# MCU.net
KiCad netlist of a schematic drawn in Altium Designer
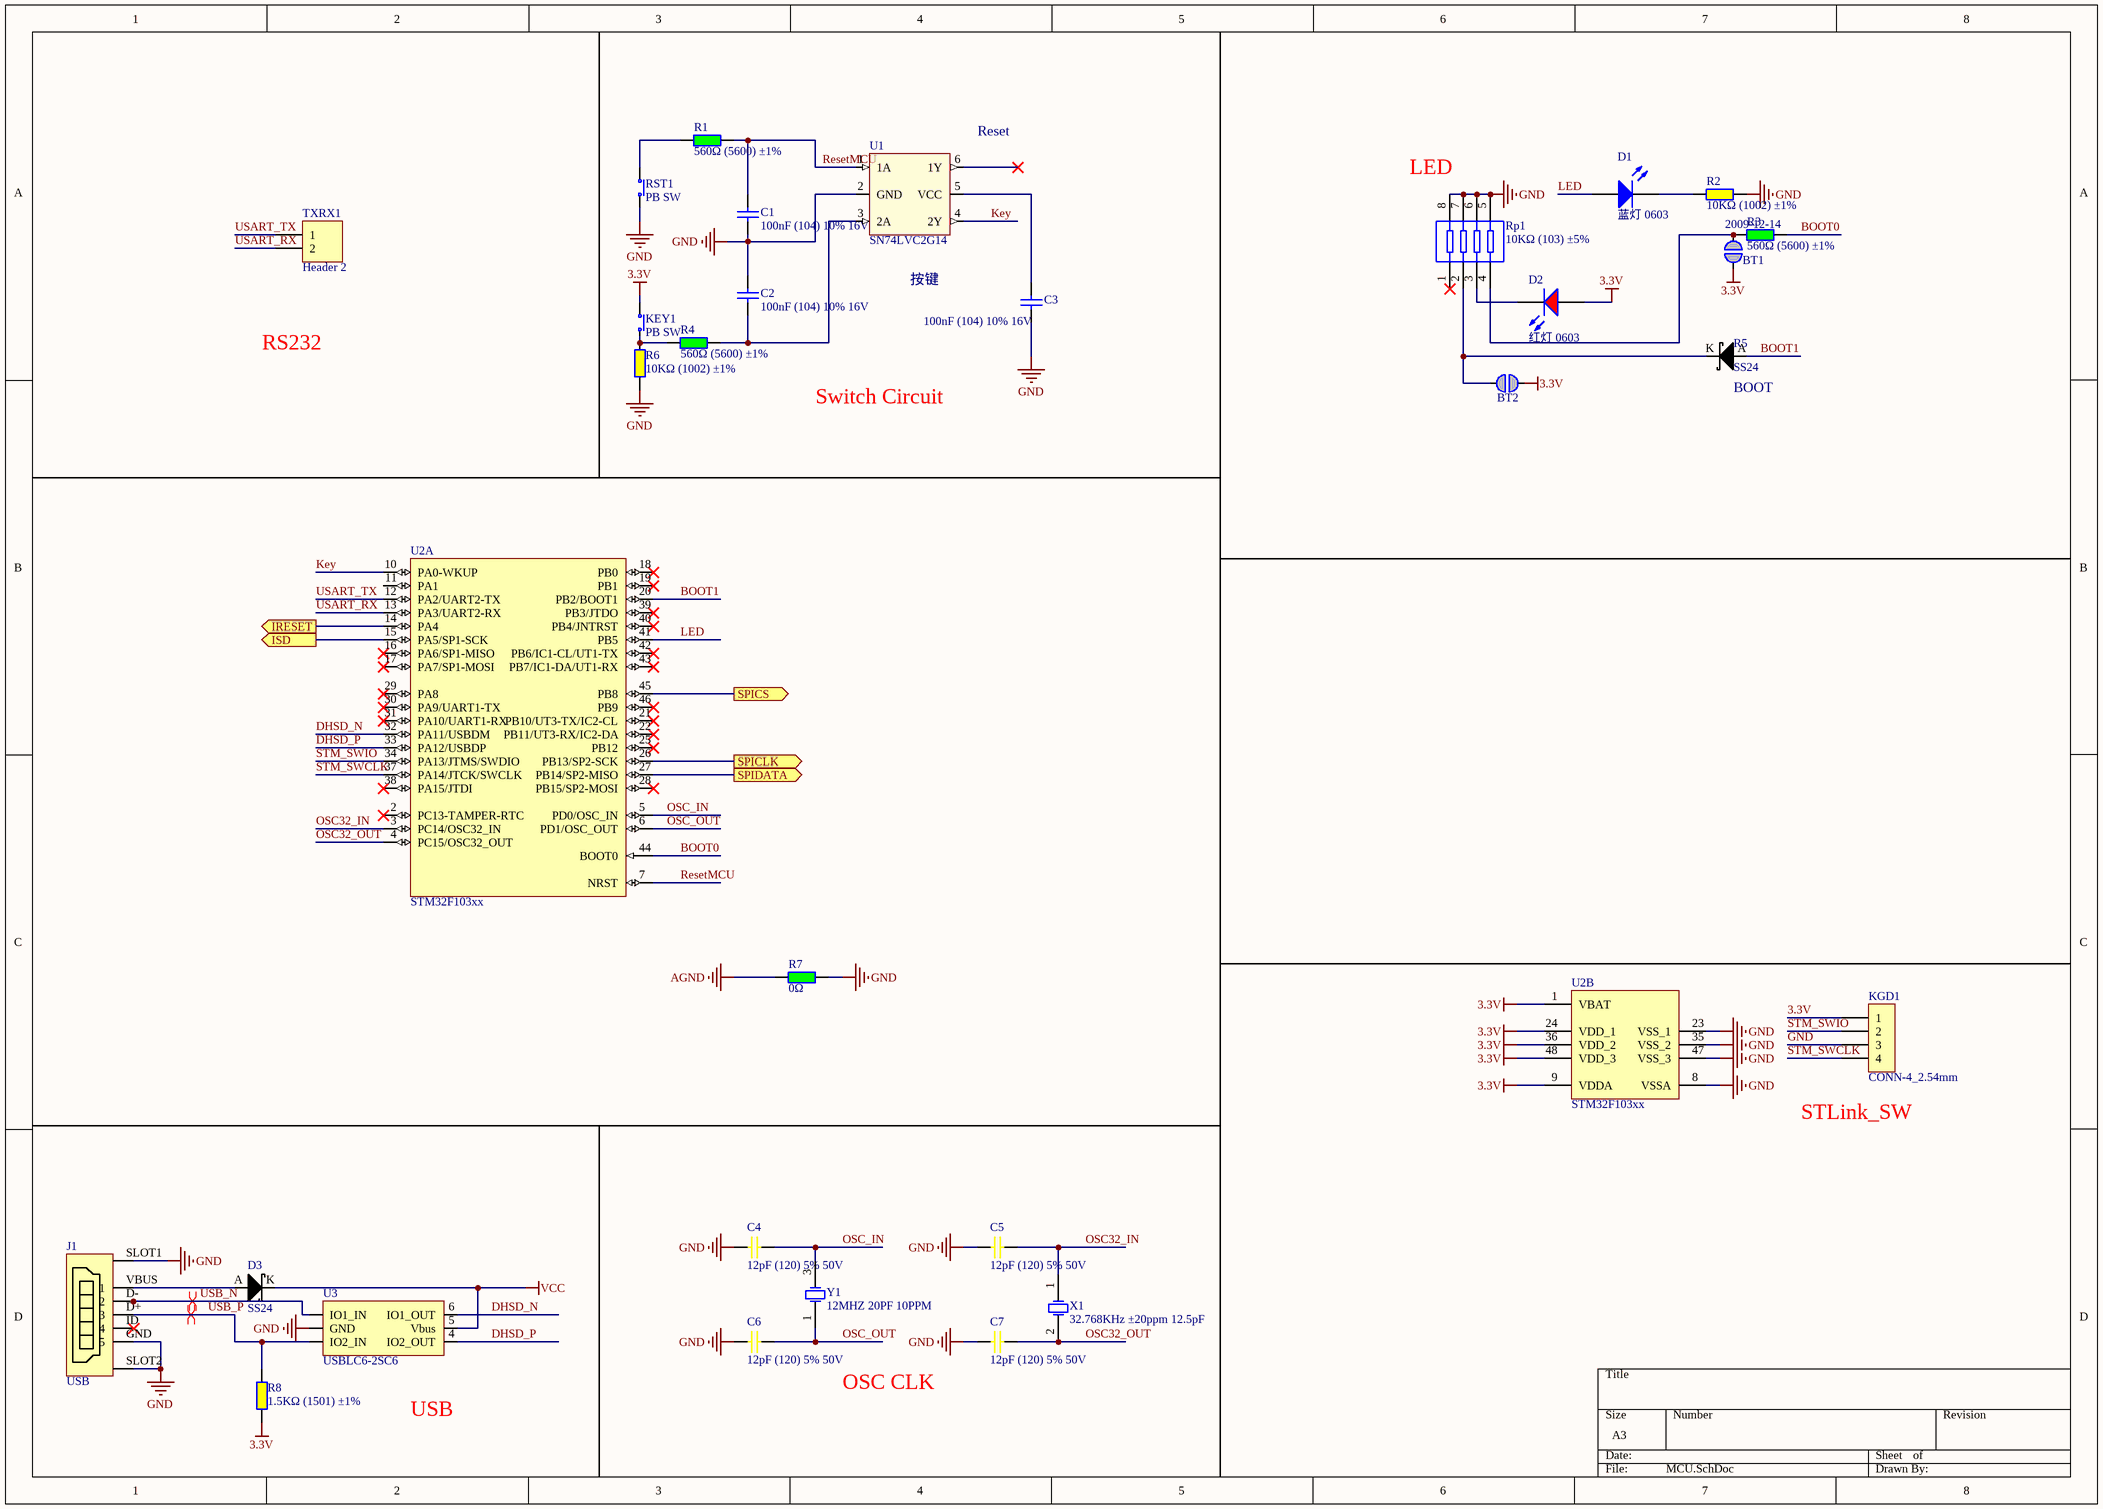
[diagram p0: MCU.SchDoc]

(export (version "E")
  (design (tool "Eeschema 10.0.6"))
  (components
    (comp (ref "BT1")
      (value "Solderbridge")
      (footprint "Solderbridge")
      (fields
        (field (name "LATESTREVISIONDATE") "2009-12-14")
        (field (name "PUBLISHER") "Nordic Semiconductor")
      )
      (libsource (lib "Schlib1") (part "SOLDERBRIDGE"))
    )
    (comp (ref "BT2")
      (value "Solderbridge")
      (footprint "Solderbridge")
      (fields (field (name "PUBLISHER") "Nordic Semiconductor"))
      (libsource (lib "Schlib1") (part "SOLDERBRIDGE"))
    )
    (comp (ref "C1")
      (value "100nF (104) 10% 16V")
      (footprint "0402_C")
      (description "贴片电容")
      (libsource (lib "Schlib1") (part "0402 100nF (104) 10% 16V"))
    )
    (comp (ref "C2")
      (value "100nF (104) 10% 16V")
      (footprint "0402_C")
      (description "贴片电容")
      (libsource (lib "Schlib1") (part "0402 100nF (104) 10% 16V"))
    )
    (comp (ref "C3")
      (value "100nF (104) 10% 16V")
      (footprint "0402_C")
      (description "贴片电容")
      (libsource (lib "Schlib1") (part "0402 100nF (104) 10% 16V"))
    )
    (comp (ref "C4")
      (value "12pF (120) 5% 50V")
      (footprint "0402_C")
      (description "贴片电容")
      (libsource (lib "Schlib1") (part "0402 12pF (120) 5% 50V"))
    )
    (comp (ref "C5")
      (value "12pF (120) 5% 50V")
      (footprint "0402_C")
      (description "贴片电容")
      (libsource (lib "Schlib1") (part "0402 12pF (120) 5% 50V"))
    )
    (comp (ref "C6")
      (value "12pF (120) 5% 50V")
      (footprint "0402_C")
      (description "贴片电容")
      (libsource (lib "Schlib1") (part "0402 12pF (120) 5% 50V"))
    )
    (comp (ref "C7")
      (value "12pF (120) 5% 50V")
      (footprint "0402_C")
      (description "贴片电容")
      (libsource (lib "Schlib1") (part "0402 12pF (120) 5% 50V"))
    )
    (comp (ref "D1")
      (value "蓝灯 0603")
      (footprint "0603_LED_S1")
      (description "发光二极管")
      (libsource (lib "LED") (part "0603 蓝灯"))
    )
    (comp (ref "D2")
      (value "红灯 0603")
      (footprint "0603_LED_S1")
      (description "发光二极管")
      (libsource (lib "LED") (part "0603 红灯"))
    )
    (comp (ref "D3")
      (value "SS24")
      (footprint "SMB-DIODE-DO214AA")
      (description "SCHOTTKY DIODE")
      (fields (field (name "MANUFACTURER") "Fairchild Semiconductor"))
      (libsource (lib "Schlib1") (part "SS24"))
    )
    (comp (ref "J1")
      (value "USB")
      (footprint "MicroUSB_SMT")
      (description "Micro-USB Type:B")
      (fields (field (name "MANUFACTURER") "精拓金"))
      (libsource (lib "Schlib1") (part "USB"))
    )
    (comp (ref "KEY1")
      (value "PB SW")
      (footprint "ALPS_SKHUxxx010_WO_GND")
      (description "Switch")
      (fields
        (field (name "MANUFACTURER") "韩国韩荣")
        (field (name "MANUFACTURER PART NUMBER") "K2-6639SP-C4SC-04")
      )
      (libsource (lib "Schlib1") (part "SW-PB_mouser"))
    )
    (comp (ref "KGD1")
      (value "CONN-4_2.54mm")
      (footprint "CON4-2.54mm")
      (description "2.54mm 4pin through hole")
      (libsource (lib "Schlib1") (part "CONN-4_2.54mm"))
    )
    (comp (ref "R1")
      (value "560Ω (5600) ±1%")
      (footprint "0603_R")
      (description "贴片电阻")
      (libsource (lib "Schlib1") (part "0603 560Ω (5600) 1%"))
    )
    (comp (ref "R2")
      (value "10KΩ (1002) ±1%")
      (footprint "0402_R")
      (description "贴片电阻")
      (libsource (lib "Schlib1") (part "0402 10KΩ (1002) 1%"))
    )
    (comp (ref "R3")
      (value "560Ω (5600) ±1%")
      (footprint "0603_R")
      (description "贴片电阻")
      (libsource (lib "Schlib1") (part "0603 560Ω (5600) 1%"))
    )
    (comp (ref "R4")
      (value "560Ω (5600) ±1%")
      (footprint "0603_R")
      (description "贴片电阻")
      (libsource (lib "Schlib1") (part "0603 560Ω (5600) 1%"))
    )
    (comp (ref "R5")
      (value "SS24")
      (footprint "SMB-DIODE-DO214AA")
      (description "SCHOTTKY DIODE")
      (fields (field (name "MANUFACTURER") "Fairchild Semiconductor"))
      (libsource (lib "Schlib1") (part "SS24"))
    )
    (comp (ref "R6")
      (value "10KΩ (1002) ±1%")
      (footprint "0402_R")
      (description "贴片电阻")
      (libsource (lib "") (part "0402 10KΩ (1002) 1%_1"))
    )
    (comp (ref "R7")
      (value "0Ω")
      (footprint "0603_R")
      (description "贴片电阻")
      (libsource (lib "Schlib1") (part "0603 0Ω"))
    )
    (comp (ref "R8")
      (value "1.5KΩ (1501) ±1%")
      (footprint "0402_R")
      (description "贴片电阻")
      (libsource (lib "Schlib1") (part "0402 1.5KΩ (1501) 1%"))
    )
    (comp (ref "Rp1")
      (value "10KΩ (103) ±5%")
      (footprint "0603_Rx4")
      (description "贴片排阻")
      (libsource (lib "Schlib1") (part "0603*4  10KΩ (103) 5%"))
    )
    (comp (ref "RST1")
      (value "PB SW")
      (footprint "ALPS_SKHUxxx010_WO_GND")
      (description "Switch")
      (fields
        (field (name "MANUFACTURER") "韩国韩荣")
        (field (name "MANUFACTURER PART NUMBER") "K2-6639SP-C4SC-04")
      )
      (libsource (lib "Schlib1") (part "SW-PB_mouser"))
    )
    (comp (ref "TXRX1")
      (value "Header 2")
      (footprint "HDR1X2")
      (description "Header, 2-Pin")
      (fields (field (name "PUBLISHER") "Altium Limited"))
      (libsource (lib "Schlib1") (part "Header 2"))
    )
    (comp (ref "U1")
      (value "SN74LVC2G14")
      (footprint "SN74LVC2G14DBVR")
      (description "74系列逻辑芯片")
      (fields (field (name "MANUFACTURER") "TI"))
      (libsource (lib "Schlib1") (part "SN74LVC2G14"))
    )
    (comp (ref "U2")
      (value "STM32F103xx")
      (footprint "PcbLib1:LQFP-48_7x7x05P")
      (description "ARM")
      (libsource (lib "Schlib1") (part "STM32F103xx"))
    )
    (comp (ref "U3")
      (value "USBLC6-2SC6")
      (footprint "SOT-23-6")
      (description "ESD二极管（静电保护）")
      (fields (field (name "MANUFACTURER") "ST"))
      (libsource (lib "Schlib1") (part "USBLC6-2SC6"))
    )
    (comp (ref "X1")
      (value "32.768KHz ±20ppm 12.5pF")
      (footprint "SMD-3215_2P FC - 135")
      (description "贴片晶振")
      (libsource (lib "CrystalOscillator") (part "SMD-3215_2P 32.768KHz 20ppm 12.5pF"))
    )
    (comp (ref "Y1")
      (value "12MHZ 20PF 10PPM")
      (footprint "SMD-3225_4P")
      (description "贴片晶振")
      (libsource (lib "CrystalOscillator") (part "SMD-3225_4P  12MHZ 20PF 10PPM"))
    )
  )
  (nets
    (net (code "1") (name "/BOOT0") (class "Default")
      (node (ref "R3") (pin "2") (pinfunction "2_2") (pintype "passive"))
      (node (ref "U2") (pin "44") (pinfunction "BOOT0_44") (pintype "input"))
    )
    (net (code "2") (name "/BOOT1") (class "Default")
      (node (ref "R5") (pin "A") (pinfunction "A_A") (pintype "passive"))
      (node (ref "U2") (pin "20") (pinfunction "PB2/BOOT1_20") (pintype "bidirectional"))
    )
    (net (code "3") (name "/DHSD_N") (class "Default")
      (node (ref "U2") (pin "32") (pinfunction "PA11/USBDM_32") (pintype "bidirectional"))
      (node (ref "U3") (pin "6") (pinfunction "IO1_OUT_6") (pintype "passive"))
    )
    (net (code "4") (name "/DHSD_P") (class "Default")
      (node (ref "U2") (pin "33") (pinfunction "PA12/USBDP_33") (pintype "bidirectional"))
      (node (ref "U3") (pin "4") (pinfunction "IO2_OUT_4") (pintype "passive"))
    )
    (net (code "5") (name "/IRESET") (class "Default")
      (node (ref "U2") (pin "14") (pinfunction "PA4_14") (pintype "bidirectional"))
    )
    (net (code "6") (name "/ISD") (class "Default")
      (node (ref "U2") (pin "15") (pinfunction "PA5/SP1-SCK_15") (pintype "bidirectional"))
    )
    (net (code "7") (name "/Key") (class "Default")
      (node (ref "U1") (pin "4") (pinfunction "2Y_4") (pintype "output"))
      (node (ref "U2") (pin "10") (pinfunction "PA0-WKUP_10") (pintype "bidirectional"))
    )
    (net (code "8") (name "/LED") (class "Default")
      (node (ref "D1") (pin "A") (pinfunction "A_A") (pintype "passive"))
      (node (ref "U2") (pin "41") (pinfunction "PB5_41") (pintype "bidirectional"))
    )
    (net (code "9") (name "/OSC32_IN") (class "Default")
      (node (ref "C5") (pin "2") (pinfunction "2_2") (pintype "passive"))
      (node (ref "U2") (pin "3") (pinfunction "PC14/OSC32_IN_3") (pintype "bidirectional"))
      (node (ref "X1") (pin "1") (pinfunction "OSC1_1") (pintype "passive"))
    )
    (net (code "10") (name "/OSC32_OUT") (class "Default")
      (node (ref "C7") (pin "2") (pinfunction "2_2") (pintype "passive"))
      (node (ref "U2") (pin "4") (pinfunction "PC15/OSC32_OUT_4") (pintype "bidirectional"))
      (node (ref "X1") (pin "2") (pinfunction "OSC2_2") (pintype "passive"))
    )
    (net (code "11") (name "/OSC_IN") (class "Default")
      (node (ref "C4") (pin "2") (pinfunction "2_2") (pintype "passive"))
      (node (ref "U2") (pin "5") (pinfunction "PD0/OSC_IN_5") (pintype "bidirectional"))
      (node (ref "Y1") (pin "3") (pinfunction "OSC2_3") (pintype "passive"))
    )
    (net (code "12") (name "/OSC_OUT") (class "Default")
      (node (ref "C6") (pin "2") (pinfunction "2_2") (pintype "passive"))
      (node (ref "U2") (pin "6") (pinfunction "PD1/OSC_OUT_6") (pintype "bidirectional"))
      (node (ref "Y1") (pin "1") (pinfunction "OSC1_1") (pintype "passive"))
    )
    (net (code "13") (name "/ResetMCU") (class "Default")
      (node (ref "C1") (pin "2") (pinfunction "2_2") (pintype "passive"))
      (node (ref "R1") (pin "2") (pinfunction "2_2") (pintype "passive"))
      (node (ref "U1") (pin "1") (pinfunction "1A_1") (pintype "input"))
      (node (ref "U2") (pin "7") (pinfunction "NRST_7") (pintype "bidirectional"))
    )
    (net (code "14") (name "/SPICLK") (class "Default")
      (node (ref "U2") (pin "26") (pinfunction "PB13/SP2-SCK_26") (pintype "bidirectional"))
    )
    (net (code "15") (name "/SPICS") (class "Default")
      (node (ref "U2") (pin "45") (pinfunction "PB8_45") (pintype "bidirectional"))
    )
    (net (code "16") (name "/SPIDATA") (class "Default")
      (node (ref "U2") (pin "27") (pinfunction "PB14/SP2-MISO_27") (pintype "bidirectional"))
    )
    (net (code "17") (name "/STM_SWCLK") (class "Default")
      (node (ref "KGD1") (pin "4") (pinfunction "4_4") (pintype "passive"))
      (node (ref "U2") (pin "37") (pinfunction "PA14/JTCK/SWCLK_37") (pintype "bidirectional"))
    )
    (net (code "18") (name "/STM_SWIO") (class "Default")
      (node (ref "KGD1") (pin "2") (pinfunction "2_2") (pintype "passive"))
      (node (ref "U2") (pin "34") (pinfunction "PA13/JTMS/SWDIO_34") (pintype "bidirectional"))
    )
    (net (code "19") (name "/USART_RX") (class "Default")
      (node (ref "TXRX1") (pin "2") (pinfunction "2_2") (pintype "passive"))
      (node (ref "U2") (pin "13") (pinfunction "PA3/UART2-RX_13") (pintype "bidirectional"))
    )
    (net (code "20") (name "/USART_TX") (class "Default")
      (node (ref "TXRX1") (pin "1") (pinfunction "1_1") (pintype "passive"))
      (node (ref "U2") (pin "12") (pinfunction "PA2/UART2-TX_12") (pintype "bidirectional"))
    )
    (net (code "21") (name "/USB_N") (class "Default")
      (node (ref "J1") (pin "D-") (pinfunction "2_D-") (pintype "passive"))
      (node (ref "U3") (pin "1") (pinfunction "IO1_IN_1") (pintype "passive"))
    )
    (net (code "22") (name "/USB_P") (class "Default")
      (node (ref "J1") (pin "D+") (pinfunction "3_D+") (pintype "passive"))
      (node (ref "R8") (pin "2") (pinfunction "2_2") (pintype "passive"))
      (node (ref "U3") (pin "3") (pinfunction "IO2_IN_3") (pintype "passive"))
    )
    (net (code "23") (name "3.3V") (class "Default")
      (node (ref "BT1") (pin "2") (pinfunction "1_2") (pintype "passive"))
      (node (ref "BT2") (pin "1") (pinfunction "0_1") (pintype "passive"))
      (node (ref "D2") (pin "A") (pinfunction "A_A") (pintype "passive"))
      (node (ref "KEY1") (pin "2") (pinfunction "COM_2") (pintype "passive"))
      (node (ref "KGD1") (pin "1") (pinfunction "1_1") (pintype "passive"))
      (node (ref "R8") (pin "1") (pinfunction "1_1") (pintype "passive"))
      (node (ref "U2") (pin "1") (pinfunction "VBAT_1") (pintype "power_in"))
      (node (ref "U2") (pin "24") (pinfunction "VDD_1_24") (pintype "power_in"))
      (node (ref "U2") (pin "36") (pinfunction "VDD_2_36") (pintype "power_in"))
      (node (ref "U2") (pin "48") (pinfunction "VDD_3_48") (pintype "power_in"))
      (node (ref "U2") (pin "9") (pinfunction "VDDA_9") (pintype "power_in"))
    )
    (net (code "24") (name "AGND") (class "Default")
      (node (ref "R7") (pin "1") (pinfunction "1_1") (pintype "passive"))
    )
    (net (code "25") (name "GND") (class "Default")
      (node (ref "C1") (pin "1") (pinfunction "1_1") (pintype "passive"))
      (node (ref "C2") (pin "2") (pinfunction "2_2") (pintype "passive"))
      (node (ref "C3") (pin "1") (pinfunction "1_1") (pintype "passive"))
      (node (ref "C4") (pin "1") (pinfunction "1_1") (pintype "passive"))
      (node (ref "C5") (pin "1") (pinfunction "1_1") (pintype "passive"))
      (node (ref "C6") (pin "1") (pinfunction "1_1") (pintype "passive"))
      (node (ref "C7") (pin "1") (pinfunction "1_1") (pintype "passive"))
      (node (ref "J1") (pin "GND") (pinfunction "5_GND") (pintype "passive"))
      (node (ref "J1") (pin "SLOT1") (pinfunction "SLOT1_SLOT1") (pintype "passive"))
      (node (ref "J1") (pin "SLOT2") (pinfunction "SLOT2_SLOT2") (pintype "passive"))
      (node (ref "KGD1") (pin "3") (pinfunction "3_3") (pintype "passive"))
      (node (ref "R2") (pin "2") (pinfunction "2_2") (pintype "passive"))
      (node (ref "R6") (pin "1") (pinfunction "1_1") (pintype "passive"))
      (node (ref "R7") (pin "2") (pinfunction "2_2") (pintype "passive"))
      (node (ref "RST1") (pin "1") (pinfunction "N.O_1") (pintype "passive"))
      (node (ref "Rp1") (pin "5") (pinfunction "5_5") (pintype "passive"))
      (node (ref "Rp1") (pin "6") (pinfunction "6_6") (pintype "passive"))
      (node (ref "Rp1") (pin "7") (pinfunction "7_7") (pintype "passive"))
      (node (ref "Rp1") (pin "8") (pinfunction "8_8") (pintype "passive"))
      (node (ref "U1") (pin "2") (pinfunction "GND_2") (pintype "passive"))
      (node (ref "U2") (pin "23") (pinfunction "VSS_1_23") (pintype "power_in"))
      (node (ref "U2") (pin "35") (pinfunction "VSS_2_35") (pintype "power_in"))
      (node (ref "U2") (pin "47") (pinfunction "VSS_3_47") (pintype "power_in"))
      (node (ref "U2") (pin "8") (pinfunction "VSSA_8") (pintype "power_in"))
      (node (ref "U3") (pin "2") (pinfunction "GND_2") (pintype "passive"))
    )
    (net (code "26") (name "Net-(BT1-0)") (class "Default")
      (node (ref "BT1") (pin "1") (pinfunction "0_1") (pintype "passive"))
      (node (ref "R3") (pin "1") (pinfunction "1_1") (pintype "passive"))
      (node (ref "Rp1") (pin "4") (pinfunction "4_4") (pintype "passive"))
    )
    (net (code "27") (name "Net-(BT2-1)") (class "Default")
      (node (ref "BT2") (pin "2") (pinfunction "1_2") (pintype "passive"))
      (node (ref "R5") (pin "K") (pinfunction "K_K") (pintype "passive"))
      (node (ref "Rp1") (pin "2") (pinfunction "2_2") (pintype "passive"))
    )
    (net (code "28") (name "Net-(D1-PadK)") (class "Default")
      (node (ref "D1") (pin "K") (pinfunction "K_K") (pintype "passive"))
      (node (ref "R2") (pin "1") (pinfunction "1_1") (pintype "passive"))
    )
    (net (code "29") (name "Net-(D2-PadK)") (class "Default")
      (node (ref "D2") (pin "K") (pinfunction "K_K") (pintype "passive"))
      (node (ref "Rp1") (pin "3") (pinfunction "3_3") (pintype "passive"))
    )
    (net (code "30") (name "Net-(J1-1)") (class "Default")
      (node (ref "D3") (pin "A") (pinfunction "A_A") (pintype "passive"))
      (node (ref "J1") (pin "VBUS") (pinfunction "1_VBUS") (pintype "passive"))
    )
    (net (code "31") (name "Net-(KEY1-N.O)") (class "Default")
      (node (ref "KEY1") (pin "1") (pinfunction "N.O_1") (pintype "passive"))
      (node (ref "R4") (pin "1") (pinfunction "1_1") (pintype "passive"))
      (node (ref "R6") (pin "2") (pinfunction "2_2") (pintype "passive"))
    )
    (net (code "32") (name "Net-(RST1-COM)") (class "Default")
      (node (ref "R1") (pin "1") (pinfunction "1_1") (pintype "passive"))
      (node (ref "RST1") (pin "2") (pinfunction "COM_2") (pintype "passive"))
    )
    (net (code "33") (name "Net-(U1-2A)") (class "Default")
      (node (ref "C2") (pin "1") (pinfunction "1_1") (pintype "passive"))
      (node (ref "R4") (pin "2") (pinfunction "2_2") (pintype "passive"))
      (node (ref "U1") (pin "3") (pinfunction "2A_3") (pintype "input"))
    )
    (net (code "34") (name "Net-(U1-VCC)") (class "Default")
      (node (ref "C3") (pin "2") (pinfunction "2_2") (pintype "passive"))
      (node (ref "U1") (pin "5") (pinfunction "VCC_5") (pintype "power_in"))
    )
    (net (code "35") (name "VCC") (class "Default")
      (node (ref "D3") (pin "K") (pinfunction "K_K") (pintype "passive"))
      (node (ref "U3") (pin "5") (pinfunction "Vbus_5") (pintype "passive"))
    )
    (net (code "36") (name "unconnected-(J1-4-PadID)") (class "Default")
      (node (ref "J1") (pin "ID") (pinfunction "4_ID") (pintype "passive+no_connect"))
    )
    (net (code "37") (name "unconnected-(Rp1-Pad1)") (class "Default")
      (node (ref "Rp1") (pin "1") (pinfunction "1_1") (pintype "passive+no_connect"))
    )
    (net (code "38") (name "unconnected-(U1-1Y-Pad6)") (class "Default")
      (node (ref "U1") (pin "6") (pinfunction "1Y_6") (pintype "output+no_connect"))
    )
    (net (code "39") (name "unconnected-(U2A-PA1-Pad11)") (class "Default")
      (node (ref "U2") (pin "11") (pinfunction "PA1_11") (pintype "bidirectional"))
    )
    (net (code "40") (name "unconnected-(U2A-PA6{slash}SP1-MISO-Pad16)") (class "Default")
      (node (ref "U2") (pin "16") (pinfunction "PA6/SP1-MISO_16") (pintype "bidirectional+no_connect"))
    )
    (net (code "41") (name "unconnected-(U2A-PA7{slash}SP1-MOSI-Pad17)") (class "Default")
      (node (ref "U2") (pin "17") (pinfunction "PA7/SP1-MOSI_17") (pintype "bidirectional+no_connect"))
    )
    (net (code "42") (name "unconnected-(U2A-PA8-Pad29)") (class "Default")
      (node (ref "U2") (pin "29") (pinfunction "PA8_29") (pintype "bidirectional+no_connect"))
    )
    (net (code "43") (name "unconnected-(U2A-PA9{slash}UART1-TX-Pad30)") (class "Default")
      (node (ref "U2") (pin "30") (pinfunction "PA9/UART1-TX_30") (pintype "bidirectional+no_connect"))
    )
    (net (code "44") (name "unconnected-(U2A-PA10{slash}UART1-RX-Pad31)") (class "Default")
      (node (ref "U2") (pin "31") (pinfunction "PA10/UART1-RX_31") (pintype "bidirectional+no_connect"))
    )
    (net (code "45") (name "unconnected-(U2A-PA15{slash}JTDI-Pad38)") (class "Default")
      (node (ref "U2") (pin "38") (pinfunction "PA15/JTDI_38") (pintype "bidirectional+no_connect"))
    )
    (net (code "46") (name "unconnected-(U2A-PB0-Pad18)") (class "Default")
      (node (ref "U2") (pin "18") (pinfunction "PB0_18") (pintype "bidirectional+no_connect"))
    )
    (net (code "47") (name "unconnected-(U2A-PB1-Pad19)") (class "Default")
      (node (ref "U2") (pin "19") (pinfunction "PB1_19") (pintype "bidirectional+no_connect"))
    )
    (net (code "48") (name "unconnected-(U2A-PB3{slash}JTDO-Pad39)") (class "Default")
      (node (ref "U2") (pin "39") (pinfunction "PB3/JTDO_39") (pintype "bidirectional+no_connect"))
    )
    (net (code "49") (name "unconnected-(U2A-PB4{slash}JNTRST-Pad40)") (class "Default")
      (node (ref "U2") (pin "40") (pinfunction "PB4/JNTRST_40") (pintype "bidirectional+no_connect"))
    )
    (net (code "50") (name "unconnected-(U2A-PB6{slash}IC1-CL{slash}UT1-TX-Pad42)") (class "Default")
      (node (ref "U2") (pin "42") (pinfunction "PB6/IC1-CL/UT1-TX_42") (pintype "bidirectional+no_connect"))
    )
    (net (code "51") (name "unconnected-(U2A-PB7{slash}IC1-DA{slash}UT1-RX-Pad43)") (class "Default")
      (node (ref "U2") (pin "43") (pinfunction "PB7/IC1-DA/UT1-RX_43") (pintype "bidirectional+no_connect"))
    )
    (net (code "52") (name "unconnected-(U2A-PB9-Pad46)") (class "Default")
      (node (ref "U2") (pin "46") (pinfunction "PB9_46") (pintype "bidirectional+no_connect"))
    )
    (net (code "53") (name "unconnected-(U2A-PB10{slash}UT3-TX{slash}IC2-CL-Pad21)") (class "Default")
      (node (ref "U2") (pin "21") (pinfunction "PB10/UT3-TX/IC2-CL_21") (pintype "bidirectional+no_connect"))
    )
    (net (code "54") (name "unconnected-(U2A-PB11{slash}UT3-RX{slash}IC2-DA-Pad22)") (class "Default")
      (node (ref "U2") (pin "22") (pinfunction "PB11/UT3-RX/IC2-DA_22") (pintype "bidirectional+no_connect"))
    )
    (net (code "55") (name "unconnected-(U2A-PB12-Pad25)") (class "Default")
      (node (ref "U2") (pin "25") (pinfunction "PB12_25") (pintype "bidirectional+no_connect"))
    )
    (net (code "56") (name "unconnected-(U2A-PB15{slash}SP2-MOSI-Pad28)") (class "Default")
      (node (ref "U2") (pin "28") (pinfunction "PB15/SP2-MOSI_28") (pintype "bidirectional+no_connect"))
    )
    (net (code "57") (name "unconnected-(U2A-PC13-TAMPER-RTC-Pad2)") (class "Default")
      (node (ref "U2") (pin "2") (pinfunction "PC13-TAMPER-RTC_2") (pintype "bidirectional+no_connect"))
    )
  )
)
